# GasALIM.net
KiCad netlist of a schematic drawn in EAGLE
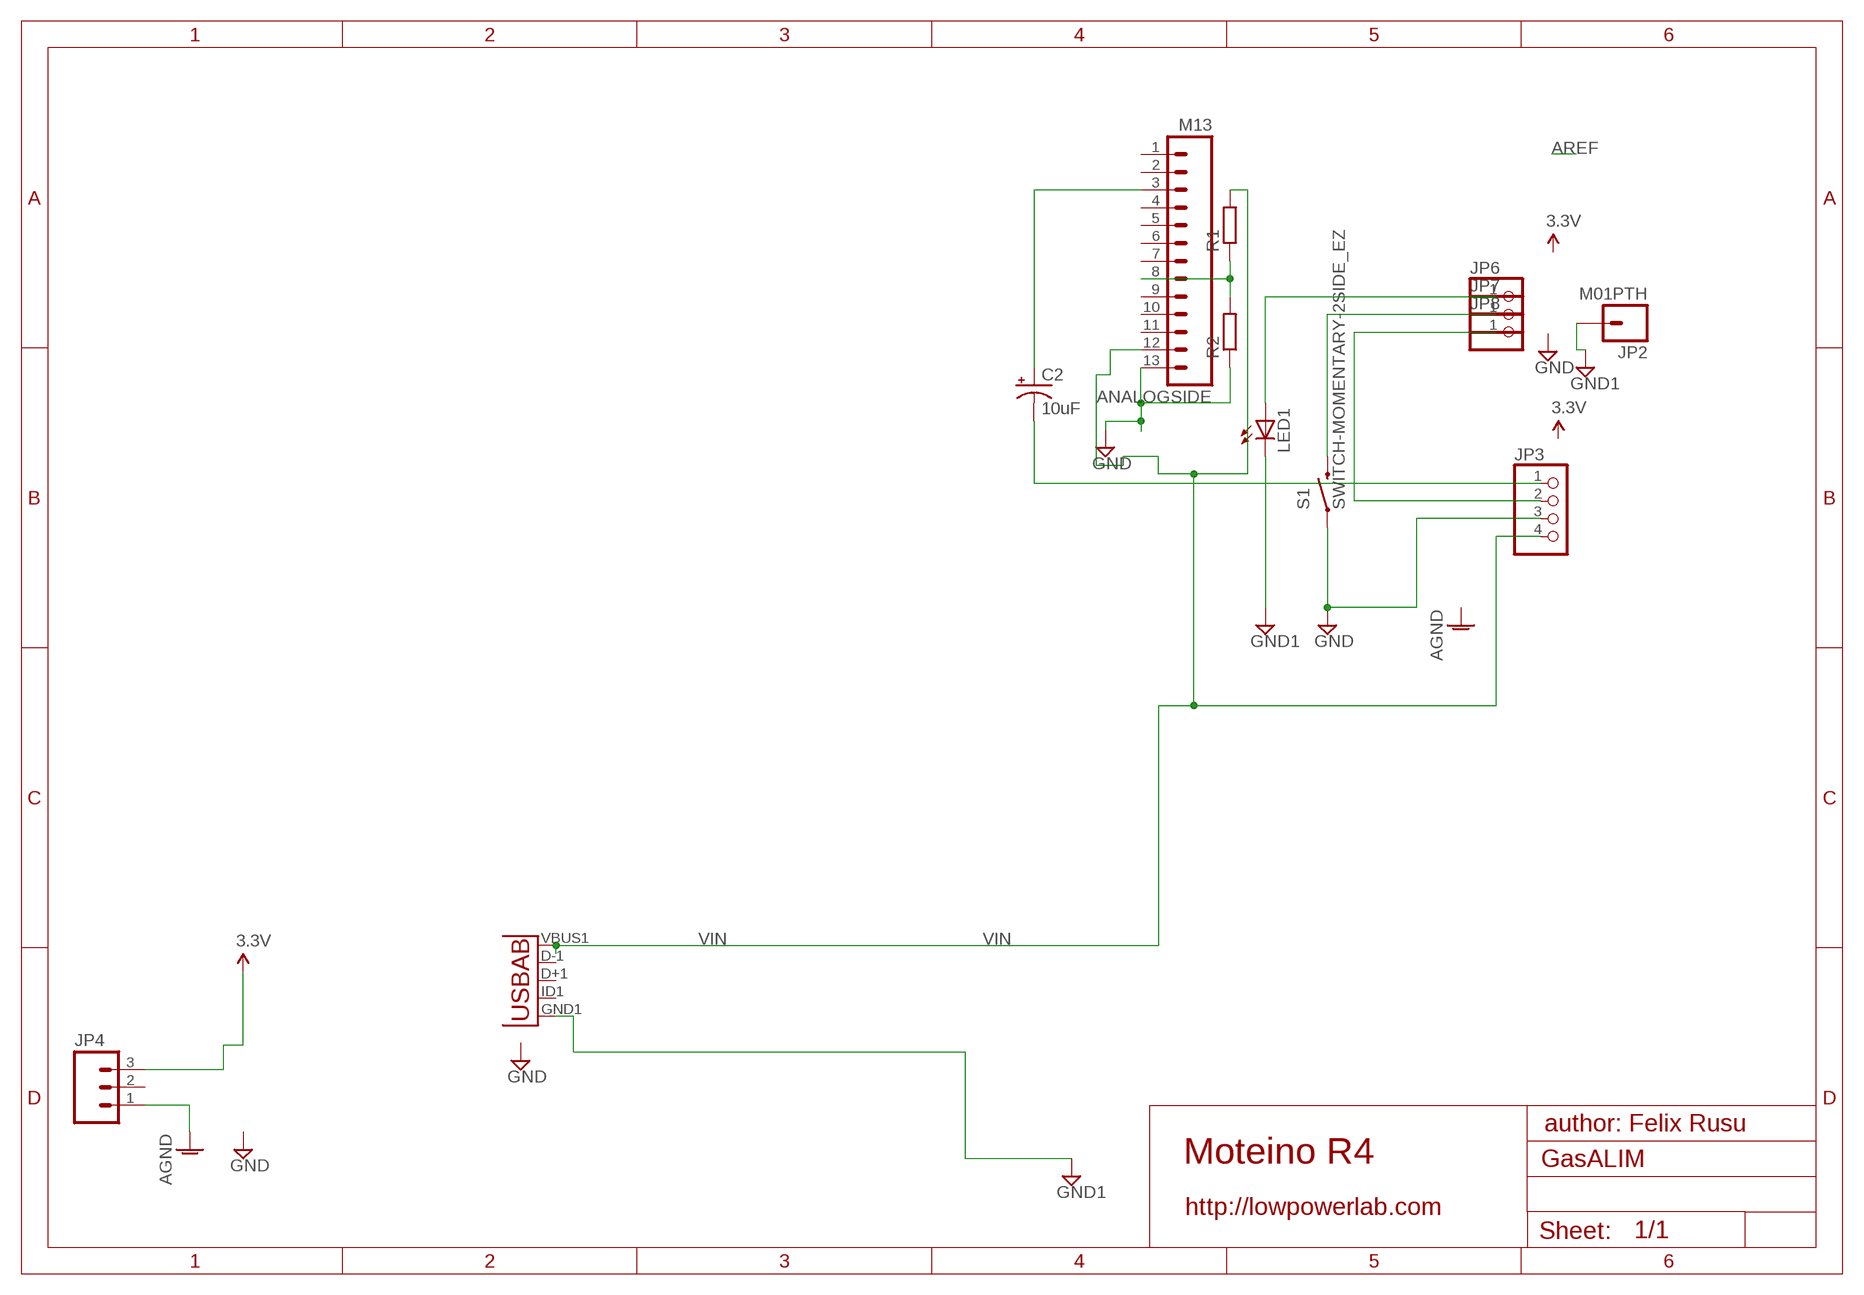
[diagram p0: schematic, sheet 1]

(export (version "E")
  (design (tool "Eeschema 10.0.6"))
  (components
    (comp (ref "ANALOGSIDE")
      (value "M13")
      (footprint "eagle-import:1X13")
      (libsource (lib "eagle-import") (part "M13"))
    )
    (comp (ref "C2")
      (value "10uF")
      (footprint "eagle-import:EIA3216")
      (libsource (lib "eagle-import") (part "10UF-16V-10%(TANT)"))
    )
    (comp (ref "JP2")
      (value "M01PTH")
      (footprint "eagle-import:1X01")
      (libsource (lib "eagle-import") (part "M01PTH"))
    )
    (comp (ref "JP3")
      (value "PINHD-1X4")
      (footprint "eagle-import:1X04")
      (libsource (lib "eagle-import") (part "PINHD-1X4"))
    )
    (comp (ref "JP4")
      (value "M03PTH")
      (footprint "eagle-import:1X03")
      (libsource (lib "eagle-import") (part "M03PTH"))
    )
    (comp (ref "JP6")
      (value "PINHD-1X1")
      (footprint "eagle-import:1X01")
      (libsource (lib "eagle-import") (part "PINHD-1X1"))
    )
    (comp (ref "JP7")
      (value "PINHD-1X1")
      (footprint "eagle-import:1X01")
      (libsource (lib "eagle-import") (part "PINHD-1X1"))
    )
    (comp (ref "JP8")
      (value "PINHD-1X1")
      (footprint "eagle-import:1X01")
      (libsource (lib "eagle-import") (part "PINHD-1X1"))
    )
    (comp (ref "JP9")
      (value "Micro USB")
      (footprint "eagle-import:USB-AB-MICRO-SMD_V03")
      (libsource (lib "eagle-import") (part "USB-ABCONN-11794"))
    )
    (comp (ref "LED1")
      (value "LED3MM")
      (footprint "eagle-import:LED3MM")
      (libsource (lib "eagle-import") (part "LED3MM"))
    )
    (comp (ref "R1")
      (value "R-EU_0204/7")
      (footprint "eagle-import:0204_7")
      (libsource (lib "eagle-import") (part "R-EU_0204/7"))
    )
    (comp (ref "R2")
      (value "R-EU_0204/7")
      (footprint "eagle-import:0204_7")
      (libsource (lib "eagle-import") (part "R-EU_0204/7"))
    )
    (comp (ref "S1")
      (value "SWITCH-MOMENTARY-2SIDE_EZ")
      (footprint "eagle-import:TACTILE-PTH-SIDEEZ")
      (libsource (lib "eagle-import") (part "SWITCH-MOMENTARY-2SIDE_EZ"))
    )
  )
  (nets
    (net (code "2") (name "/VIN") (class "Default")
      (node (ref "ANALOGSIDE") (pin "12") (pinfunction "12_12") (pintype "passive"))
      (node (ref "JP3") (pin "4") (pinfunction "4_4") (pintype "passive"))
      (node (ref "JP9") (pin "VBUS1") (pinfunction "VBUS_VBUS1") (pintype "bidirectional"))
      (node (ref "R1") (pin "2") (pinfunction "2_2") (pintype "passive"))
    )
    (net (code "3") (name "3.3V") (class "Default")
      (node (ref "JP4") (pin "3") (pinfunction "3_3") (pintype "passive"))
    )
    (net (code "4") (name "AGND") (class "Default")
      (node (ref "JP4") (pin "1") (pinfunction "1_1") (pintype "passive"))
    )
    (net (code "5") (name "GND") (class "Default")
      (node (ref "ANALOGSIDE") (pin "13") (pinfunction "13_13") (pintype "passive"))
      (node (ref "JP3") (pin "3") (pinfunction "3_3") (pintype "passive"))
      (node (ref "R2") (pin "1") (pinfunction "1_1") (pintype "passive"))
      (node (ref "S1") (pin "1") (pinfunction "1_1") (pintype "passive"))
    )
    (net (code "6") (name "GND1") (class "Default")
      (node (ref "JP2") (pin "1") (pinfunction "1_1") (pintype "passive"))
      (node (ref "JP9") (pin "GND1") (pinfunction "GND_GND1") (pintype "bidirectional"))
      (node (ref "LED1") (pin "K") (pinfunction "C_K") (pintype "passive"))
    )
    (net (code "7") (name "Net-(ANALOGSIDE-Pad8)") (class "Default")
      (node (ref "ANALOGSIDE") (pin "8") (pinfunction "8_8") (pintype "passive"))
      (node (ref "R1") (pin "1") (pinfunction "1_1") (pintype "passive"))
      (node (ref "R2") (pin "2") (pinfunction "2_2") (pintype "passive"))
    )
    (net (code "8") (name "Net-(C2-+)") (class "Default")
      (node (ref "ANALOGSIDE") (pin "3") (pinfunction "3_3") (pintype "passive"))
      (node (ref "C2") (pin "A") (pinfunction "+_A") (pintype "passive"))
    )
    (net (code "9") (name "Net-(C2--)") (class "Default")
      (node (ref "C2") (pin "C") (pinfunction "-_C") (pintype "passive"))
      (node (ref "JP3") (pin "1") (pinfunction "1_1") (pintype "passive"))
    )
    (net (code "10") (name "Net-(JP3-Pad2)") (class "Default")
      (node (ref "JP3") (pin "2") (pinfunction "2_2") (pintype "passive"))
      (node (ref "JP8") (pin "1") (pinfunction "1_1") (pintype "passive"))
    )
    (net (code "11") (name "Net-(JP6-Pad1)") (class "Default")
      (node (ref "JP6") (pin "1") (pinfunction "1_1") (pintype "passive"))
      (node (ref "LED1") (pin "A") (pinfunction "A_A") (pintype "passive"))
    )
    (net (code "12") (name "Net-(JP7-Pad1)") (class "Default")
      (node (ref "JP7") (pin "1") (pinfunction "1_1") (pintype "passive"))
      (node (ref "S1") (pin "2") (pinfunction "2_2") (pintype "passive"))
    )
    (net (code "13") (name "unconnected-(ANALOGSIDE-Pad1)") (class "Default")
      (node (ref "ANALOGSIDE") (pin "1") (pinfunction "1_1") (pintype "passive"))
    )
    (net (code "14") (name "unconnected-(ANALOGSIDE-Pad2)") (class "Default")
      (node (ref "ANALOGSIDE") (pin "2") (pinfunction "2_2") (pintype "passive"))
    )
    (net (code "15") (name "unconnected-(ANALOGSIDE-Pad4)") (class "Default")
      (node (ref "ANALOGSIDE") (pin "4") (pinfunction "4_4") (pintype "passive"))
    )
    (net (code "16") (name "unconnected-(ANALOGSIDE-Pad5)") (class "Default")
      (node (ref "ANALOGSIDE") (pin "5") (pinfunction "5_5") (pintype "passive"))
    )
    (net (code "17") (name "unconnected-(ANALOGSIDE-Pad6)") (class "Default")
      (node (ref "ANALOGSIDE") (pin "6") (pinfunction "6_6") (pintype "passive"))
    )
    (net (code "18") (name "unconnected-(ANALOGSIDE-Pad7)") (class "Default")
      (node (ref "ANALOGSIDE") (pin "7") (pinfunction "7_7") (pintype "passive"))
    )
    (net (code "19") (name "unconnected-(ANALOGSIDE-Pad9)") (class "Default")
      (node (ref "ANALOGSIDE") (pin "9") (pinfunction "9_9") (pintype "passive"))
    )
    (net (code "20") (name "unconnected-(ANALOGSIDE-Pad10)") (class "Default")
      (node (ref "ANALOGSIDE") (pin "10") (pinfunction "10_10") (pintype "passive"))
    )
    (net (code "21") (name "unconnected-(ANALOGSIDE-Pad11)") (class "Default")
      (node (ref "ANALOGSIDE") (pin "11") (pinfunction "11_11") (pintype "passive"))
    )
    (net (code "22") (name "unconnected-(JP4-Pad2)") (class "Default")
      (node (ref "JP4") (pin "2") (pinfunction "2_2") (pintype "passive"))
    )
    (net (code "23") (name "unconnected-(JP9-D+-PadD+1)") (class "Default")
      (node (ref "JP9") (pin "D+1") (pinfunction "D+_D+1") (pintype "bidirectional"))
    )
    (net (code "24") (name "unconnected-(JP9-D--PadD-1)") (class "Default")
      (node (ref "JP9") (pin "D-1") (pinfunction "D-_D-1") (pintype "bidirectional"))
    )
    (net (code "25") (name "unconnected-(JP9-USBID-PadID1)") (class "Default")
      (node (ref "JP9") (pin "ID1") (pinfunction "USBID_ID1") (pintype "bidirectional"))
    )
  )
)
